# fat51ud.net
KiCad netlist of a schematic drawn in Altium Designer
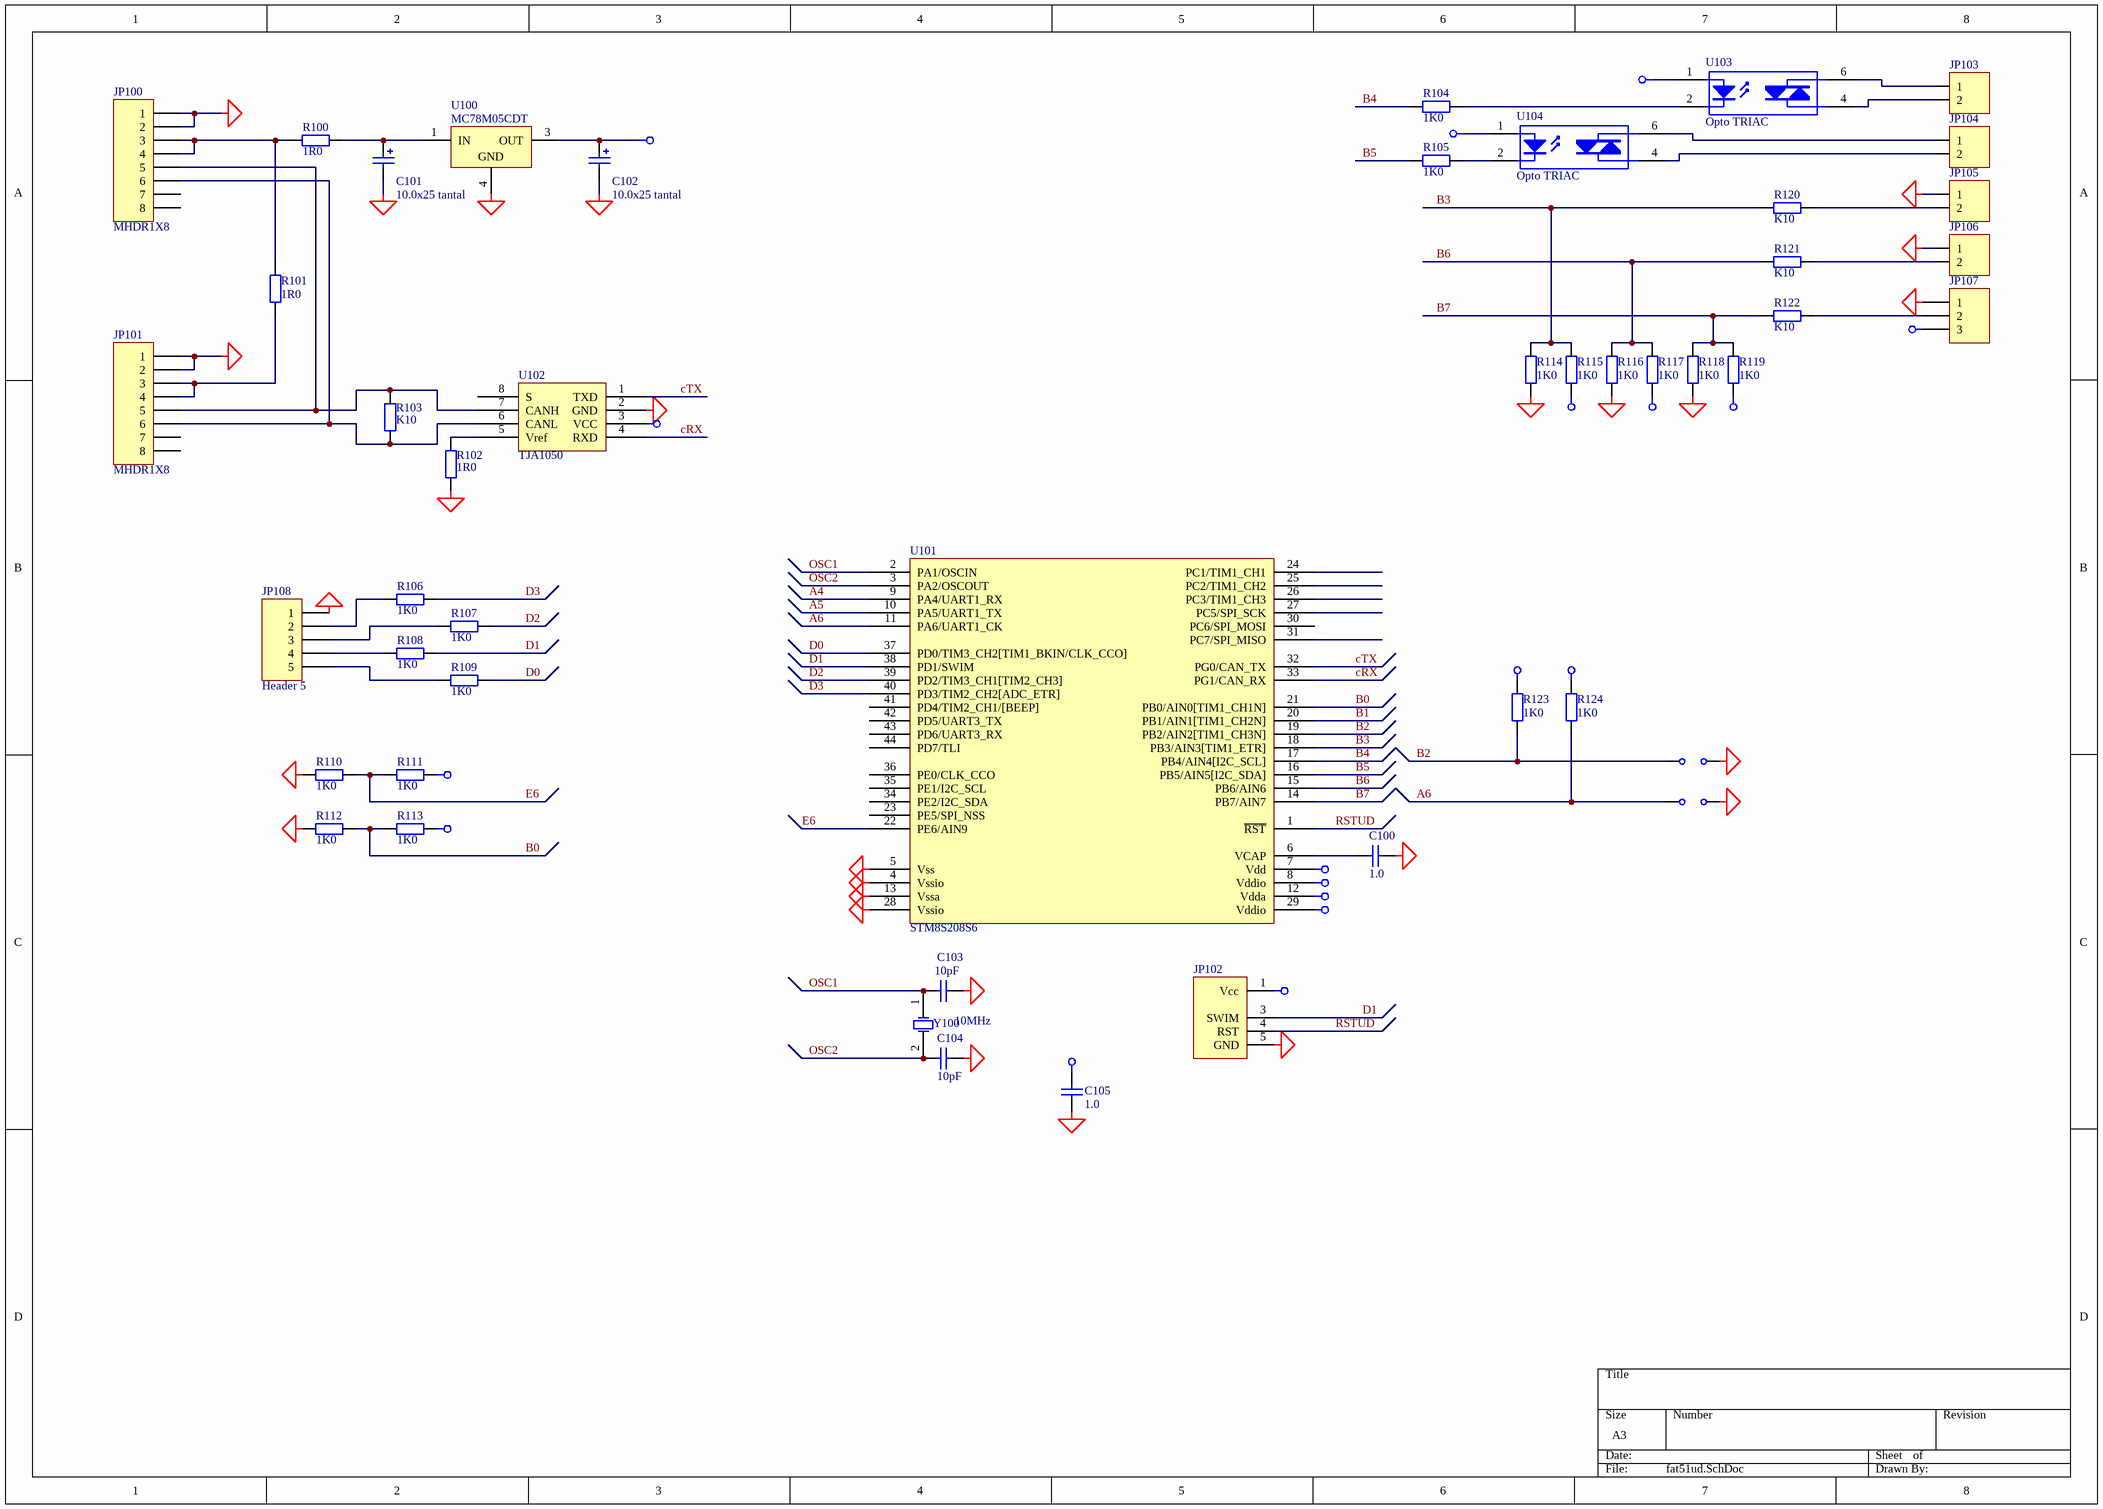
[diagram p0: fat51ud.SchDoc]

(export (version "E")
  (design (tool "Eeschema 10.0.6"))
  (components
    (comp (ref "C100")
      (value "1.0")
      (footprint "_0805")
      (description "Capacitor (Semiconductor SIM Model)")
      (fields (field (name "MANUFACTURER") "Generic Components") (field (name "PUBLISHER") "Altium Limited"))
      (libsource (lib "Miscellaneous Devices") (part "Cap Semi"))
    )
    (comp (ref "C101")
      (value "10.0x25 tantal")
      (footprint "CAP_EL_6_3")
      (description "Polarized Capacitor (Radial)")
      (fields (field (name "MANUFACTURER") "Generic Components") (field (name "PUBLISHER") "Altium Limited"))
      (libsource (lib "PAL") (part "Cap Pol1"))
    )
    (comp (ref "C102")
      (value "10.0x25 tantal")
      (footprint "CAP_EL_6_3")
      (description "Polarized Capacitor (Radial)")
      (fields (field (name "MANUFACTURER") "Generic Components") (field (name "PUBLISHER") "Altium Limited"))
      (libsource (lib "PAL") (part "Cap Pol1"))
    )
    (comp (ref "C103")
      (value "10pF")
      (footprint "_0805")
      (description "Capacitor (Semiconductor SIM Model)")
      (fields (field (name "MANUFACTURER") "Generic Components") (field (name "PUBLISHER") "Altium Limited"))
      (libsource (lib "Miscellaneous Devices") (part "Cap Semi"))
    )
    (comp (ref "C104")
      (value "10pF")
      (footprint "_0805")
      (description "Capacitor (Semiconductor SIM Model)")
      (fields (field (name "MANUFACTURER") "Generic Components") (field (name "PUBLISHER") "Altium Limited"))
      (libsource (lib "Miscellaneous Devices") (part "Cap Semi"))
    )
    (comp (ref "C105")
      (value "1.0")
      (footprint "_0805")
      (description "Capacitor (Semiconductor SIM Model)")
      (fields (field (name "MANUFACTURER") "Generic Components") (field (name "PUBLISHER") "Altium Limited"))
      (libsource (lib "Miscellaneous Devices") (part "Cap Semi"))
    )
    (comp (ref "J1")
      (value "~")
      (footprint "jmp")
      (description "Switch")
      (fields (field (name "MANUFACTURER") "Generic Components") (field (name "PUBLISHER") "Altium Limited"))
      (libsource (lib "PAL") (part "JMP"))
    )
    (comp (ref "J2")
      (value "~")
      (footprint "jmp")
      (description "Switch")
      (fields (field (name "MANUFACTURER") "Generic Components") (field (name "PUBLISHER") "Altium Limited"))
      (libsource (lib "PAL") (part "JMP"))
    )
    (comp (ref "JP100")
      (value "MHDR1X8")
      (footprint "8i8p-5306")
      (description "Header, 8-Pin")
      (fields (field (name "MANUFACTURER") "Generic Components") (field (name "PUBLISHER") "Altium Limited"))
      (libsource (lib "Miscellaneous Connectors") (part "MHDR1X8"))
    )
    (comp (ref "JP101")
      (value "MHDR1X8")
      (footprint "8i8p-5306")
      (description "Header, 8-Pin")
      (fields (field (name "MANUFACTURER") "Generic Components") (field (name "PUBLISHER") "Altium Limited"))
      (libsource (lib "Miscellaneous Connectors") (part "MHDR1X8"))
    )
    (comp (ref "JP102") (value "~") (footprint "HDR1X5_uart") (libsource (lib "PAL") (part "SWIM_CONN")))
    (comp (ref "JP103")
      (value "BT5-2")
      (footprint "BT5-2-1")
      (description "Header, 3-Pin")
      (fields (field (name "MANUFACTURER") "Generic Components") (field (name "PUBLISHER") "Altium Limited"))
      (libsource (lib "PAL") (part "BT5-2"))
    )
    (comp (ref "JP104")
      (value "BT5-2")
      (footprint "BT5-2-1")
      (description "Header, 3-Pin")
      (fields (field (name "MANUFACTURER") "Generic Components") (field (name "PUBLISHER") "Altium Limited"))
      (libsource (lib "PAL") (part "BT5-2"))
    )
    (comp (ref "JP105")
      (value "BT5-2")
      (footprint "BT5-2-1")
      (description "Header, 3-Pin")
      (fields (field (name "MANUFACTURER") "Generic Components") (field (name "PUBLISHER") "Altium Limited"))
      (libsource (lib "PAL") (part "BT5-2"))
    )
    (comp (ref "JP106")
      (value "BT5-2")
      (footprint "BT5-2-1")
      (description "Header, 3-Pin")
      (fields (field (name "MANUFACTURER") "Generic Components") (field (name "PUBLISHER") "Altium Limited"))
      (libsource (lib "PAL") (part "BT5-2"))
    )
    (comp (ref "JP107")
      (value "Header 3")
      (footprint "BT5-3")
      (description "Header, 3-Pin")
      (fields (field (name "MANUFACTURER") "Generic Components") (field (name "PUBLISHER") "Altium Limited"))
      (libsource (lib "Miscellaneous Connectors") (part "Header 3"))
    )
    (comp (ref "JP108")
      (value "Header 5")
      (footprint "HDR1X5")
      (description "Header, 5-Pin")
      (fields (field (name "MANUFACTURER") "Generic Components") (field (name "PUBLISHER") "Altium Limited"))
      (libsource (lib "Miscellaneous Connectors") (part "Header 5"))
    )
    (comp (ref "R100")
      (value "1R0")
      (footprint "_0805")
      (description "Resistor")
      (fields (field (name "MANUFACTURER") "Generic Components") (field (name "PUBLISHER") "Altium Limited"))
      (libsource (lib "") (part "Res2_1"))
    )
    (comp (ref "R101")
      (value "1R0")
      (footprint "_0805")
      (description "Resistor")
      (fields (field (name "MANUFACTURER") "Generic Components") (field (name "PUBLISHER") "Altium Limited"))
      (libsource (lib "") (part "Res2_4"))
    )
    (comp (ref "R102")
      (value "1R0")
      (footprint "_0805")
      (description "Resistor")
      (fields (field (name "MANUFACTURER") "Generic Components") (field (name "PUBLISHER") "Altium Limited"))
      (libsource (lib "") (part "Res2_1"))
    )
    (comp (ref "R103")
      (value "K10")
      (footprint "_0805")
      (description "Resistor")
      (fields (field (name "MANUFACTURER") "Generic Components") (field (name "PUBLISHER") "Altium Limited"))
      (libsource (lib "") (part "Res2_1"))
    )
    (comp (ref "R104")
      (value "1K0")
      (footprint "_0805")
      (description "Resistor")
      (fields (field (name "MANUFACTURER") "Generic Components") (field (name "PUBLISHER") "Altium Limited"))
      (libsource (lib "Miscellaneous Devices") (part "Res2"))
    )
    (comp (ref "R105")
      (value "1K0")
      (footprint "_0805")
      (description "Resistor")
      (fields (field (name "MANUFACTURER") "Generic Components") (field (name "PUBLISHER") "Altium Limited"))
      (libsource (lib "Miscellaneous Devices") (part "Res2"))
    )
    (comp (ref "R106")
      (value "1K0")
      (footprint "_0805")
      (description "Resistor")
      (fields (field (name "MANUFACTURER") "Generic Components") (field (name "PUBLISHER") "Altium Limited"))
      (libsource (lib "Miscellaneous Devices") (part "Res2"))
    )
    (comp (ref "R107")
      (value "1K0")
      (footprint "_0805")
      (description "Resistor")
      (fields (field (name "MANUFACTURER") "Generic Components") (field (name "PUBLISHER") "Altium Limited"))
      (libsource (lib "Miscellaneous Devices") (part "Res2"))
    )
    (comp (ref "R108")
      (value "1K0")
      (footprint "_0805")
      (description "Resistor")
      (fields (field (name "MANUFACTURER") "Generic Components") (field (name "PUBLISHER") "Altium Limited"))
      (libsource (lib "Miscellaneous Devices") (part "Res2"))
    )
    (comp (ref "R109")
      (value "1K0")
      (footprint "_0805")
      (description "Resistor")
      (fields (field (name "MANUFACTURER") "Generic Components") (field (name "PUBLISHER") "Altium Limited"))
      (libsource (lib "Miscellaneous Devices") (part "Res2"))
    )
    (comp (ref "R110")
      (value "1K0")
      (footprint "_0805")
      (description "Resistor")
      (fields (field (name "MANUFACTURER") "Generic Components") (field (name "PUBLISHER") "Altium Limited"))
      (libsource (lib "Miscellaneous Devices") (part "Res2"))
    )
    (comp (ref "R111")
      (value "1K0")
      (footprint "_0805")
      (description "Resistor")
      (fields (field (name "MANUFACTURER") "Generic Components") (field (name "PUBLISHER") "Altium Limited"))
      (libsource (lib "Miscellaneous Devices") (part "Res2"))
    )
    (comp (ref "R112")
      (value "1K0")
      (footprint "_0805")
      (description "Resistor")
      (fields (field (name "MANUFACTURER") "Generic Components") (field (name "PUBLISHER") "Altium Limited"))
      (libsource (lib "Miscellaneous Devices") (part "Res2"))
    )
    (comp (ref "R113")
      (value "1K0")
      (footprint "_0805")
      (description "Resistor")
      (fields (field (name "MANUFACTURER") "Generic Components") (field (name "PUBLISHER") "Altium Limited"))
      (libsource (lib "Miscellaneous Devices") (part "Res2"))
    )
    (comp (ref "R114")
      (value "1K0")
      (footprint "_0805")
      (description "Resistor")
      (fields (field (name "MANUFACTURER") "Generic Components") (field (name "PUBLISHER") "Altium Limited"))
      (libsource (lib "") (part "Res2_3"))
    )
    (comp (ref "R115")
      (value "1K0")
      (footprint "_0805")
      (description "Resistor")
      (fields (field (name "MANUFACTURER") "Generic Components") (field (name "PUBLISHER") "Altium Limited"))
      (libsource (lib "") (part "Res2_3"))
    )
    (comp (ref "R116")
      (value "1K0")
      (footprint "_0805")
      (description "Resistor")
      (fields (field (name "MANUFACTURER") "Generic Components") (field (name "PUBLISHER") "Altium Limited"))
      (libsource (lib "") (part "Res2_3"))
    )
    (comp (ref "R117")
      (value "1K0")
      (footprint "_0805")
      (description "Resistor")
      (fields (field (name "MANUFACTURER") "Generic Components") (field (name "PUBLISHER") "Altium Limited"))
      (libsource (lib "") (part "Res2_3"))
    )
    (comp (ref "R118")
      (value "1K0")
      (footprint "_0805")
      (description "Resistor")
      (fields (field (name "MANUFACTURER") "Generic Components") (field (name "PUBLISHER") "Altium Limited"))
      (libsource (lib "") (part "Res2_3"))
    )
    (comp (ref "R119")
      (value "1K0")
      (footprint "_0805")
      (description "Resistor")
      (fields (field (name "MANUFACTURER") "Generic Components") (field (name "PUBLISHER") "Altium Limited"))
      (libsource (lib "") (part "Res2_3"))
    )
    (comp (ref "R120")
      (value "K10")
      (footprint "_0805")
      (description "Resistor")
      (fields (field (name "MANUFACTURER") "Generic Components") (field (name "PUBLISHER") "Altium Limited"))
      (libsource (lib "") (part "Res2_2"))
    )
    (comp (ref "R121")
      (value "K10")
      (footprint "_0805")
      (description "Resistor")
      (fields (field (name "MANUFACTURER") "Generic Components") (field (name "PUBLISHER") "Altium Limited"))
      (libsource (lib "") (part "Res2_2"))
    )
    (comp (ref "R122")
      (value "K10")
      (footprint "_0805")
      (description "Resistor")
      (fields (field (name "MANUFACTURER") "Generic Components") (field (name "PUBLISHER") "Altium Limited"))
      (libsource (lib "") (part "Res2_2"))
    )
    (comp (ref "R123")
      (value "1K0")
      (footprint "_0805")
      (description "Resistor")
      (fields (field (name "MANUFACTURER") "Generic Components") (field (name "PUBLISHER") "Altium Limited"))
      (libsource (lib "") (part "Res2_3"))
    )
    (comp (ref "R124")
      (value "1K0")
      (footprint "_0805")
      (description "Resistor")
      (fields (field (name "MANUFACTURER") "Generic Components") (field (name "PUBLISHER") "Altium Limited"))
      (libsource (lib "") (part "Res2_3"))
    )
    (comp (ref "U100")
      (value "MC78M05CDT")
      (footprint "SIP-G3/Z11.05")
      (description "Three-Terminal Medium Current Positive Voltage Regulator")
      (fields (field (name "MANUFACTURER") "ON Semiconductor") (field (name "PUBLISHER") "Altium Limited"))
      (libsource (lib "ON Semi Power Mgt Voltage Regulator") (part "MC78M05CDT"))
    )
    (comp (ref "U101")
      (value "STM8S208S6")
      (footprint "QFP10X10-G44/G10N")
      (libsource (lib "PAL") (part "STM8S208S6"))
    )
    (comp (ref "U102") (value "TJA1050") (footprint "SO-G8/D5") (libsource (lib "PAL") (part "TJA1050")))
    (comp (ref "U103")
      (value "Opto TRIAC")
      (footprint "dip-6")
      (description "Opto-Triac")
      (fields (field (name "MANUFACTURER") "Generic Components") (field (name "PUBLISHER") "Altium Limited"))
      (libsource (lib "PAL") (part "Opto TRIAC"))
    )
    (comp (ref "U104")
      (value "Opto TRIAC")
      (footprint "dip-6")
      (description "Opto-Triac")
      (fields (field (name "MANUFACTURER") "Generic Components") (field (name "PUBLISHER") "Altium Limited"))
      (libsource (lib "PAL") (part "Opto TRIAC"))
    )
    (comp (ref "Y100")
      (value "10MHz")
      (footprint "QWARZ1")
      (description "Crystal Oscillator")
      (fields (field (name "MANUFACTURER") "Generic Components") (field (name "PUBLISHER") "Altium Limited"))
      (libsource (lib "Miscellaneous Devices") (part "XTAL"))
    )
  )
  (nets
    (net (code "1") (name "+5v_ud") (class "Default")
      (node (ref "C102") (pin "1") (pinfunction "1_1") (pintype "passive"))
      (node (ref "C105") (pin "1") (pinfunction "1_1") (pintype "passive"))
      (node (ref "JP102") (pin "1") (pinfunction "Vcc_1") (pintype "passive"))
      (node (ref "JP107") (pin "3") (pinfunction "3_3") (pintype "passive"))
      (node (ref "R111") (pin "1") (pinfunction "1_1") (pintype "passive"))
      (node (ref "R113") (pin "1") (pinfunction "1_1") (pintype "passive"))
      (node (ref "R115") (pin "2") (pinfunction "2_2") (pintype "passive"))
      (node (ref "R117") (pin "2") (pinfunction "2_2") (pintype "passive"))
      (node (ref "R119") (pin "2") (pinfunction "2_2") (pintype "passive"))
      (node (ref "R123") (pin "1") (pinfunction "1_1") (pintype "passive"))
      (node (ref "R124") (pin "1") (pinfunction "1_1") (pintype "passive"))
      (node (ref "U100") (pin "3") (pinfunction "OUT_3") (pintype "power_in"))
      (node (ref "U101") (pin "12") (pinfunction "Vdda_12") (pintype "passive"))
      (node (ref "U101") (pin "29") (pinfunction "Vddio_29") (pintype "passive"))
      (node (ref "U101") (pin "7") (pinfunction "Vdd_7") (pintype "passive"))
      (node (ref "U101") (pin "8") (pinfunction "Vddio_8") (pintype "passive"))
      (node (ref "U102") (pin "3") (pinfunction "VCC_3") (pintype "passive"))
      (node (ref "U103") (pin "1") (pinfunction "A_1") (pintype "passive"))
      (node (ref "U104") (pin "1") (pinfunction "A_1") (pintype "passive"))
    )
    (net (code "2") (name "/A4") (class "Default")
      (node (ref "U101") (pin "9") (pinfunction "PA4/UART1_RX_9") (pintype "passive"))
    )
    (net (code "3") (name "/A5") (class "Default")
      (node (ref "U101") (pin "10") (pinfunction "PA5/UART1_TX_10") (pintype "passive"))
    )
    (net (code "4") (name "/A6") (class "Default")
      (node (ref "J1") (pin "2") (pinfunction "2_2") (pintype "passive"))
      (node (ref "R124") (pin "2") (pinfunction "2_2") (pintype "passive"))
      (node (ref "U101") (pin "11") (pinfunction "PA6/UART1_CK_11") (pintype "passive"))
    )
    (net (code "5") (name "/B0") (class "Default")
      (node (ref "R112") (pin "1") (pinfunction "1_1") (pintype "passive"))
      (node (ref "R113") (pin "2") (pinfunction "2_2") (pintype "passive"))
      (node (ref "U101") (pin "21") (pinfunction "PB0/AIN0[TIM1_CH1N]_21") (pintype "passive"))
    )
    (net (code "6") (name "/B1") (class "Default")
      (node (ref "U101") (pin "20") (pinfunction "PB1/AIN1[TIM1_CH2N]_20") (pintype "passive"))
    )
    (net (code "7") (name "/B2") (class "Default")
      (node (ref "J2") (pin "2") (pinfunction "2_2") (pintype "passive"))
      (node (ref "R123") (pin "2") (pinfunction "2_2") (pintype "passive"))
      (node (ref "U101") (pin "19") (pinfunction "PB2/AIN2[TIM1_CH3N]_19") (pintype "passive"))
    )
    (net (code "8") (name "/B3") (class "Default")
      (node (ref "R114") (pin "1") (pinfunction "1_1") (pintype "passive"))
      (node (ref "R115") (pin "1") (pinfunction "1_1") (pintype "passive"))
      (node (ref "R120") (pin "2") (pinfunction "2_2") (pintype "passive"))
      (node (ref "U101") (pin "18") (pinfunction "PB3/AIN3[TIM1_ETR]_18") (pintype "passive"))
    )
    (net (code "9") (name "/B4") (class "Default")
      (node (ref "R104") (pin "2") (pinfunction "2_2") (pintype "passive"))
      (node (ref "U101") (pin "17") (pinfunction "PB4/AIN4[I2C_SCL]_17") (pintype "passive"))
    )
    (net (code "10") (name "/B5") (class "Default")
      (node (ref "R105") (pin "2") (pinfunction "2_2") (pintype "passive"))
      (node (ref "U101") (pin "16") (pinfunction "PB5/AIN5[I2C_SDA]_16") (pintype "passive"))
    )
    (net (code "11") (name "/B6") (class "Default")
      (node (ref "R116") (pin "1") (pinfunction "1_1") (pintype "passive"))
      (node (ref "R117") (pin "1") (pinfunction "1_1") (pintype "passive"))
      (node (ref "R121") (pin "2") (pinfunction "2_2") (pintype "passive"))
      (node (ref "U101") (pin "15") (pinfunction "PB6/AIN6_15") (pintype "passive"))
    )
    (net (code "12") (name "/B7") (class "Default")
      (node (ref "R118") (pin "1") (pinfunction "1_1") (pintype "passive"))
      (node (ref "R119") (pin "1") (pinfunction "1_1") (pintype "passive"))
      (node (ref "R122") (pin "2") (pinfunction "2_2") (pintype "passive"))
      (node (ref "U101") (pin "14") (pinfunction "PB7/AIN7_14") (pintype "passive"))
    )
    (net (code "13") (name "/D0") (class "Default")
      (node (ref "R109") (pin "1") (pinfunction "1_1") (pintype "passive"))
      (node (ref "U101") (pin "37") (pinfunction "PD0/TIM3_CH2[TIM1_BKIN/CLK_CCO]_37") (pintype "passive"))
    )
    (net (code "14") (name "/D1") (class "Default")
      (node (ref "JP102") (pin "3") (pinfunction "SWIM_3") (pintype "passive"))
      (node (ref "R108") (pin "1") (pinfunction "1_1") (pintype "passive"))
      (node (ref "U101") (pin "38") (pinfunction "PD1/SWIM_38") (pintype "passive"))
    )
    (net (code "15") (name "/D2") (class "Default")
      (node (ref "R107") (pin "1") (pinfunction "1_1") (pintype "passive"))
      (node (ref "U101") (pin "39") (pinfunction "PD2/TIM3_CH1[TIM2_CH3]_39") (pintype "passive"))
    )
    (net (code "16") (name "/D3") (class "Default")
      (node (ref "R106") (pin "1") (pinfunction "1_1") (pintype "passive"))
      (node (ref "U101") (pin "40") (pinfunction "PD3/TIM2_CH2[ADC_ETR]_40") (pintype "passive"))
    )
    (net (code "17") (name "/E6") (class "Default")
      (node (ref "R110") (pin "1") (pinfunction "1_1") (pintype "passive"))
      (node (ref "R111") (pin "2") (pinfunction "2_2") (pintype "passive"))
      (node (ref "U101") (pin "22") (pinfunction "PE6/AIN9_22") (pintype "passive"))
    )
    (net (code "18") (name "/OSC1") (class "Default")
      (node (ref "C103") (pin "2") (pinfunction "2_2") (pintype "passive"))
      (node (ref "U101") (pin "2") (pinfunction "PA1/OSCIN_2") (pintype "passive"))
      (node (ref "Y100") (pin "1") (pinfunction "OSC1_1") (pintype "passive"))
    )
    (net (code "19") (name "/OSC2") (class "Default")
      (node (ref "C104") (pin "2") (pinfunction "2_2") (pintype "passive"))
      (node (ref "U101") (pin "3") (pinfunction "PA2/OSCOUT_3") (pintype "passive"))
      (node (ref "Y100") (pin "2") (pinfunction "OSC2_2") (pintype "passive"))
    )
    (net (code "20") (name "/RSTUD") (class "Default")
      (node (ref "JP102") (pin "4") (pinfunction "RST_4") (pintype "passive"))
      (node (ref "U101") (pin "1") (pinfunction "~{RST}_1") (pintype "passive"))
    )
    (net (code "21") (name "/cRX") (class "Default")
      (node (ref "U101") (pin "33") (pinfunction "PG1/CAN_RX_33") (pintype "passive"))
      (node (ref "U102") (pin "4") (pinfunction "RXD_4") (pintype "passive"))
    )
    (net (code "22") (name "/cTX") (class "Default")
      (node (ref "U101") (pin "32") (pinfunction "PG0/CAN_TX_32") (pintype "passive"))
      (node (ref "U102") (pin "1") (pinfunction "TXD_1") (pintype "passive"))
    )
    (net (code "23") (name "GNDUD") (class "Default")
      (node (ref "C100") (pin "1") (pinfunction "1_1") (pintype "passive"))
      (node (ref "C101") (pin "2") (pinfunction "2_2") (pintype "passive"))
      (node (ref "C102") (pin "2") (pinfunction "2_2") (pintype "passive"))
      (node (ref "C103") (pin "1") (pinfunction "1_1") (pintype "passive"))
      (node (ref "C104") (pin "1") (pinfunction "1_1") (pintype "passive"))
      (node (ref "C105") (pin "2") (pinfunction "2_2") (pintype "passive"))
      (node (ref "J1") (pin "1") (pinfunction "1_1") (pintype "passive"))
      (node (ref "J2") (pin "1") (pinfunction "1_1") (pintype "passive"))
      (node (ref "JP100") (pin "1") (pinfunction "1_1") (pintype "passive"))
      (node (ref "JP100") (pin "2") (pinfunction "2_2") (pintype "passive"))
      (node (ref "JP101") (pin "1") (pinfunction "1_1") (pintype "passive"))
      (node (ref "JP101") (pin "2") (pinfunction "2_2") (pintype "passive"))
      (node (ref "JP102") (pin "5") (pinfunction "GND_5") (pintype "passive"))
      (node (ref "JP105") (pin "1") (pinfunction "1_1") (pintype "passive"))
      (node (ref "JP106") (pin "1") (pinfunction "1_1") (pintype "passive"))
      (node (ref "JP107") (pin "1") (pinfunction "1_1") (pintype "passive"))
      (node (ref "JP108") (pin "1") (pinfunction "1_1") (pintype "passive"))
      (node (ref "R102") (pin "1") (pinfunction "1_1") (pintype "passive"))
      (node (ref "R110") (pin "2") (pinfunction "2_2") (pintype "passive"))
      (node (ref "R112") (pin "2") (pinfunction "2_2") (pintype "passive"))
      (node (ref "R114") (pin "2") (pinfunction "2_2") (pintype "passive"))
      (node (ref "R116") (pin "2") (pinfunction "2_2") (pintype "passive"))
      (node (ref "R118") (pin "2") (pinfunction "2_2") (pintype "passive"))
      (node (ref "U100") (pin "4") (pinfunction "GND_4") (pintype "power_in"))
      (node (ref "U101") (pin "13") (pinfunction "Vssa_13") (pintype "passive"))
      (node (ref "U101") (pin "28") (pinfunction "Vssio_28") (pintype "passive"))
      (node (ref "U101") (pin "4") (pinfunction "Vssio_4") (pintype "passive"))
      (node (ref "U102") (pin "2") (pinfunction "GND_2") (pintype "passive"))
    )
    (net (code "24") (name "Net-(JP100-Pad3)") (class "Default")
      (node (ref "JP100") (pin "3") (pinfunction "3_3") (pintype "passive"))
      (node (ref "JP100") (pin "4") (pinfunction "4_4") (pintype "passive"))
      (node (ref "R100") (pin "1") (pinfunction "1_1") (pintype "passive"))
      (node (ref "R101") (pin "2") (pinfunction "2_2") (pintype "passive"))
    )
    (net (code "25") (name "Net-(JP101-Pad3)") (class "Default")
      (node (ref "JP101") (pin "3") (pinfunction "3_3") (pintype "passive"))
      (node (ref "JP101") (pin "4") (pinfunction "4_4") (pintype "passive"))
      (node (ref "R101") (pin "1") (pinfunction "1_1") (pintype "passive"))
    )
    (net (code "26") (name "Net-(JP103-Pad1)") (class "Default")
      (node (ref "JP103") (pin "1") (pinfunction "1_1") (pintype "passive"))
      (node (ref "U103") (pin "6") (pinfunction "A/K_6") (pintype "passive"))
    )
    (net (code "27") (name "Net-(JP103-Pad2)") (class "Default")
      (node (ref "JP103") (pin "2") (pinfunction "2_2") (pintype "passive"))
      (node (ref "U103") (pin "4") (pinfunction "A/K_4") (pintype "passive"))
    )
    (net (code "28") (name "Net-(JP104-Pad1)") (class "Default")
      (node (ref "JP104") (pin "1") (pinfunction "1_1") (pintype "passive"))
      (node (ref "U104") (pin "6") (pinfunction "A/K_6") (pintype "passive"))
    )
    (net (code "29") (name "Net-(JP104-Pad2)") (class "Default")
      (node (ref "JP104") (pin "2") (pinfunction "2_2") (pintype "passive"))
      (node (ref "U104") (pin "4") (pinfunction "A/K_4") (pintype "passive"))
    )
    (net (code "30") (name "Net-(JP105-Pad2)") (class "Default")
      (node (ref "JP105") (pin "2") (pinfunction "2_2") (pintype "passive"))
      (node (ref "R120") (pin "1") (pinfunction "1_1") (pintype "passive"))
    )
    (net (code "31") (name "Net-(JP106-Pad2)") (class "Default")
      (node (ref "JP106") (pin "2") (pinfunction "2_2") (pintype "passive"))
      (node (ref "R121") (pin "1") (pinfunction "1_1") (pintype "passive"))
    )
    (net (code "32") (name "Net-(JP107-Pad2)") (class "Default")
      (node (ref "JP107") (pin "2") (pinfunction "2_2") (pintype "passive"))
      (node (ref "R122") (pin "1") (pinfunction "1_1") (pintype "passive"))
    )
    (net (code "33") (name "Net-(JP108-Pad2)") (class "Default")
      (node (ref "JP108") (pin "2") (pinfunction "2_2") (pintype "passive"))
      (node (ref "R106") (pin "2") (pinfunction "2_2") (pintype "passive"))
    )
    (net (code "34") (name "Net-(JP108-Pad3)") (class "Default")
      (node (ref "JP108") (pin "3") (pinfunction "3_3") (pintype "passive"))
      (node (ref "R107") (pin "2") (pinfunction "2_2") (pintype "passive"))
    )
    (net (code "35") (name "Net-(JP108-Pad4)") (class "Default")
      (node (ref "JP108") (pin "4") (pinfunction "4_4") (pintype "passive"))
      (node (ref "R108") (pin "2") (pinfunction "2_2") (pintype "passive"))
    )
    (net (code "36") (name "Net-(JP108-Pad5)") (class "Default")
      (node (ref "JP108") (pin "5") (pinfunction "5_5") (pintype "passive"))
      (node (ref "R109") (pin "2") (pinfunction "2_2") (pintype "passive"))
    )
    (net (code "37") (name "Net-(U100-IN)") (class "Default")
      (node (ref "C101") (pin "1") (pinfunction "1_1") (pintype "passive"))
      (node (ref "R100") (pin "2") (pinfunction "2_2") (pintype "passive"))
      (node (ref "U100") (pin "1") (pinfunction "IN_1") (pintype "power_in"))
    )
    (net (code "38") (name "Net-(U101-VCAP)") (class "Default")
      (node (ref "C100") (pin "2") (pinfunction "2_2") (pintype "passive"))
      (node (ref "U101") (pin "6") (pinfunction "VCAP_6") (pintype "passive"))
    )
    (net (code "39") (name "Net-(U102-CANH)") (class "Default")
      (node (ref "JP100") (pin "5") (pinfunction "5_5") (pintype "passive"))
      (node (ref "JP101") (pin "5") (pinfunction "5_5") (pintype "passive"))
      (node (ref "R103") (pin "2") (pinfunction "2_2") (pintype "passive"))
      (node (ref "U102") (pin "7") (pinfunction "CANH_7") (pintype "passive"))
    )
    (net (code "40") (name "Net-(U102-CANL)") (class "Default")
      (node (ref "JP100") (pin "6") (pinfunction "6_6") (pintype "passive"))
      (node (ref "JP101") (pin "6") (pinfunction "6_6") (pintype "passive"))
      (node (ref "R103") (pin "1") (pinfunction "1_1") (pintype "passive"))
      (node (ref "U102") (pin "6") (pinfunction "CANL_6") (pintype "passive"))
    )
    (net (code "41") (name "Net-(U102-Vref)") (class "Default")
      (node (ref "R102") (pin "2") (pinfunction "2_2") (pintype "passive"))
      (node (ref "U102") (pin "5") (pinfunction "Vref_5") (pintype "passive"))
    )
    (net (code "42") (name "Net-(U103-K)") (class "Default")
      (node (ref "R104") (pin "1") (pinfunction "1_1") (pintype "passive"))
      (node (ref "U103") (pin "2") (pinfunction "K_2") (pintype "passive"))
    )
    (net (code "43") (name "Net-(U104-K)") (class "Default")
      (node (ref "R105") (pin "1") (pinfunction "1_1") (pintype "passive"))
      (node (ref "U104") (pin "2") (pinfunction "K_2") (pintype "passive"))
    )
    (net (code "44") (name "UD") (class "Default")
      (node (ref "U101") (pin "5") (pinfunction "Vss_5") (pintype "passive"))
    )
    (net (code "45") (name "unconnected-(JP100-Pad7)") (class "Default")
      (node (ref "JP100") (pin "7") (pinfunction "7_7") (pintype "passive"))
    )
    (net (code "46") (name "unconnected-(JP100-Pad8)") (class "Default")
      (node (ref "JP100") (pin "8") (pinfunction "8_8") (pintype "passive"))
    )
    (net (code "47") (name "unconnected-(JP101-Pad7)") (class "Default")
      (node (ref "JP101") (pin "7") (pinfunction "7_7") (pintype "passive"))
    )
    (net (code "48") (name "unconnected-(JP101-Pad8)") (class "Default")
      (node (ref "JP101") (pin "8") (pinfunction "8_8") (pintype "passive"))
    )
    (net (code "49") (name "unconnected-(U101-PC1{slash}TIM1_CH1-Pad24)") (class "Default")
      (node (ref "U101") (pin "24") (pinfunction "PC1/TIM1_CH1_24") (pintype "passive"))
    )
    (net (code "50") (name "unconnected-(U101-PC2{slash}TIM1_CH2-Pad25)") (class "Default")
      (node (ref "U101") (pin "25") (pinfunction "PC2/TIM1_CH2_25") (pintype "passive"))
    )
    (net (code "51") (name "unconnected-(U101-PC3{slash}TIM1_CH3-Pad26)") (class "Default")
      (node (ref "U101") (pin "26") (pinfunction "PC3/TIM1_CH3_26") (pintype "passive"))
    )
    (net (code "52") (name "unconnected-(U101-PC5{slash}SPI_SCK-Pad27)") (class "Default")
      (node (ref "U101") (pin "27") (pinfunction "PC5/SPI_SCK_27") (pintype "passive"))
    )
    (net (code "53") (name "unconnected-(U101-PC6{slash}SPI_MOSI-Pad30)") (class "Default")
      (node (ref "U101") (pin "30") (pinfunction "PC6/SPI_MOSI_30") (pintype "passive"))
    )
    (net (code "54") (name "unconnected-(U101-PC7{slash}SPI_MISO-Pad31)") (class "Default")
      (node (ref "U101") (pin "31") (pinfunction "PC7/SPI_MISO_31") (pintype "passive"))
    )
    (net (code "55") (name "unconnected-(U101-PD4{slash}TIM2_CH1{slash}[BEEP]-Pad41)") (class "Default")
      (node (ref "U101") (pin "41") (pinfunction "PD4/TIM2_CH1/[BEEP]_41") (pintype "passive"))
    )
    (net (code "56") (name "unconnected-(U101-PD5{slash}UART3_TX-Pad42)") (class "Default")
      (node (ref "U101") (pin "42") (pinfunction "PD5/UART3_TX_42") (pintype "passive"))
    )
    (net (code "57") (name "unconnected-(U101-PD6{slash}UART3_RX-Pad43)") (class "Default")
      (node (ref "U101") (pin "43") (pinfunction "PD6/UART3_RX_43") (pintype "passive"))
    )
    (net (code "58") (name "unconnected-(U101-PD7{slash}TLI-Pad44)") (class "Default")
      (node (ref "U101") (pin "44") (pinfunction "PD7/TLI_44") (pintype "passive"))
    )
    (net (code "59") (name "unconnected-(U101-PE0{slash}CLK_CCO-Pad36)") (class "Default")
      (node (ref "U101") (pin "36") (pinfunction "PE0/CLK_CCO_36") (pintype "passive"))
    )
    (net (code "60") (name "unconnected-(U101-PE1{slash}I2C_SCL-Pad35)") (class "Default")
      (node (ref "U101") (pin "35") (pinfunction "PE1/I2C_SCL_35") (pintype "passive"))
    )
    (net (code "61") (name "unconnected-(U101-PE2{slash}I2C_SDA-Pad34)") (class "Default")
      (node (ref "U101") (pin "34") (pinfunction "PE2/I2C_SDA_34") (pintype "passive"))
    )
    (net (code "62") (name "unconnected-(U101-PE5{slash}SPI_NSS-Pad23)") (class "Default")
      (node (ref "U101") (pin "23") (pinfunction "PE5/SPI_NSS_23") (pintype "passive"))
    )
    (net (code "63") (name "unconnected-(U102-S-Pad8)") (class "Default")
      (node (ref "U102") (pin "8") (pinfunction "S_8") (pintype "passive"))
    )
  )
)
